# ADC.net
KiCad netlist of a schematic drawn in Altium Designer
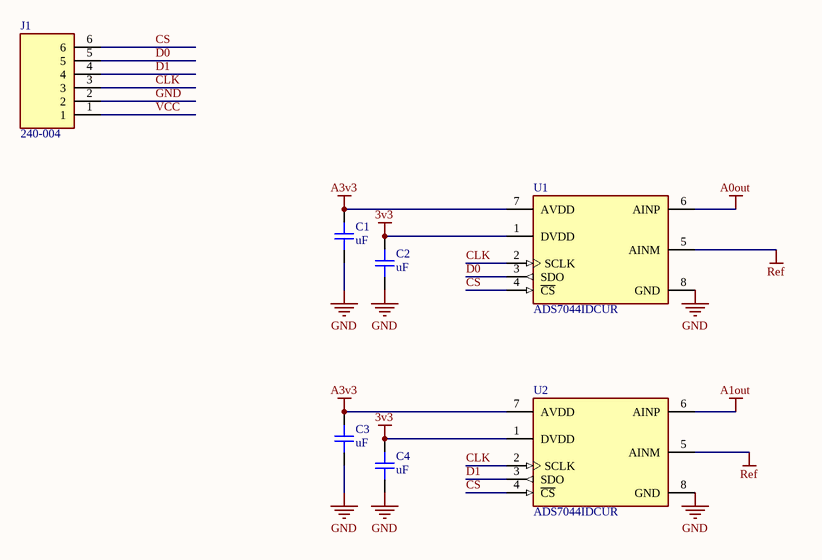
[diagram p0: ADC.SchDoc]

(export (version "E")
  (design (tool "Eeschema 10.0.6"))
  (components
    (comp (ref "C1")
      (value "uF")
      (footprint "CAP_0603")
      (description "Capacitor SMD 0603")
      (libsource (lib "Schematic-Lib-PhilsLab") (part "CAP_0603"))
    )
    (comp (ref "C2")
      (value "uF")
      (footprint "CAP_0603")
      (description "Capacitor SMD 0603")
      (libsource (lib "Schematic-Lib-PhilsLab") (part "CAP_0603"))
    )
    (comp (ref "C3")
      (value "uF")
      (footprint "CAP_0603")
      (description "Capacitor SMD 0603")
      (libsource (lib "Schematic-Lib-PhilsLab") (part "CAP_0603"))
    )
    (comp (ref "C4")
      (value "uF")
      (footprint "CAP_0603")
      (description "Capacitor SMD 0603")
      (libsource (lib "Schematic-Lib-PhilsLab") (part "CAP_0603"))
    )
    (comp (ref "J1")
      (value "240-004")
      (footprint "SamacSys:HDRV6W64P0X254_1X6_1524X254X909P")
      (description "Connector")
      (libsource (lib "*") (part "240-004"))
    )
    (comp (ref "U1")
      (value "ADS7044IDCUR")
      (footprint "FP-DCU0008A-MFG")
      (description "IC ADC 12BIT SAR 8VSSOP")
      (libsource (lib "Altium Content Vault") (part "9a0bc509c7babeb6aac5c1e79e84b2f"))
    )
    (comp (ref "U2")
      (value "ADS7044IDCUR")
      (footprint "FP-DCU0008A-MFG")
      (description "IC ADC 12BIT SAR 8VSSOP")
      (libsource (lib "Altium Content Vault") (part "9a0bc509c7babeb6aac5c1e79e84b2f"))
    )
  )
  (nets
    (net (code "1") (name "/CLK") (class "Default")
      (node (ref "J1") (pin "3") (pinfunction "3_3") (pintype "passive"))
      (node (ref "U1") (pin "2") (pinfunction "SCLK_2") (pintype "input"))
      (node (ref "U2") (pin "2") (pinfunction "SCLK_2") (pintype "input"))
    )
    (net (code "2") (name "/CS") (class "Default")
      (node (ref "J1") (pin "6") (pinfunction "6_6") (pintype "passive"))
      (node (ref "U1") (pin "4") (pinfunction "~{CS}_4") (pintype "input"))
      (node (ref "U2") (pin "4") (pinfunction "~{CS}_4") (pintype "input"))
    )
    (net (code "3") (name "/D0") (class "Default")
      (node (ref "J1") (pin "5") (pinfunction "5_5") (pintype "passive"))
      (node (ref "U1") (pin "3") (pinfunction "SDO_3") (pintype "output"))
    )
    (net (code "4") (name "/D1") (class "Default")
      (node (ref "J1") (pin "4") (pinfunction "4_4") (pintype "passive"))
      (node (ref "U2") (pin "3") (pinfunction "SDO_3") (pintype "output"))
    )
    (net (code "5") (name "/VCC") (class "Default")
      (node (ref "J1") (pin "1") (pinfunction "1_1") (pintype "passive"))
    )
    (net (code "6") (name "3v3") (class "Default")
      (node (ref "C2") (pin "2") (pinfunction "2_2") (pintype "passive"))
      (node (ref "C4") (pin "2") (pinfunction "2_2") (pintype "passive"))
      (node (ref "U1") (pin "1") (pinfunction "DVDD_1") (pintype "power_in"))
      (node (ref "U2") (pin "1") (pinfunction "DVDD_1") (pintype "power_in"))
    )
    (net (code "7") (name "A0out") (class "Default")
      (node (ref "U1") (pin "6") (pinfunction "AINP_6") (pintype "passive"))
    )
    (net (code "8") (name "A1out") (class "Default")
      (node (ref "U2") (pin "6") (pinfunction "AINP_6") (pintype "passive"))
    )
    (net (code "9") (name "A3v3") (class "Default")
      (node (ref "C1") (pin "2") (pinfunction "2_2") (pintype "passive"))
      (node (ref "C3") (pin "2") (pinfunction "2_2") (pintype "passive"))
      (node (ref "U1") (pin "7") (pinfunction "AVDD_7") (pintype "power_in"))
      (node (ref "U2") (pin "7") (pinfunction "AVDD_7") (pintype "power_in"))
    )
    (net (code "10") (name "GND") (class "Default")
      (node (ref "C1") (pin "1") (pinfunction "1_1") (pintype "passive"))
      (node (ref "C2") (pin "1") (pinfunction "1_1") (pintype "passive"))
      (node (ref "C3") (pin "1") (pinfunction "1_1") (pintype "passive"))
      (node (ref "C4") (pin "1") (pinfunction "1_1") (pintype "passive"))
      (node (ref "J1") (pin "2") (pinfunction "2_2") (pintype "passive"))
      (node (ref "U1") (pin "8") (pinfunction "GND_8") (pintype "power_in"))
      (node (ref "U2") (pin "8") (pinfunction "GND_8") (pintype "power_in"))
    )
    (net (code "11") (name "Ref") (class "Default")
      (node (ref "U1") (pin "5") (pinfunction "AINM_5") (pintype "passive"))
      (node (ref "U2") (pin "5") (pinfunction "AINM_5") (pintype "passive"))
    )
  )
)
